# wk3-practice.net
KiCad netlist of a schematic drawn in EAGLE
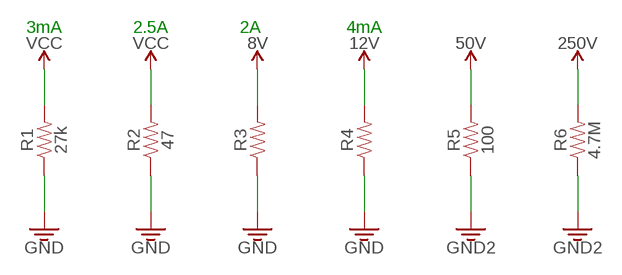
[diagram p0: schematic, sheet 1]

(export (version "E")
  (design (tool "Eeschema 10.0.6"))
  (components
    (comp (ref "R1")
      (value "27k")
      (footprint "eagle-import:AXIAL-0.3")
      (libsource (lib "eagle-import") (part "RESISTORAXIAL-0.3"))
    )
    (comp (ref "R2")
      (value "47")
      (footprint "eagle-import:AXIAL-0.3")
      (libsource (lib "eagle-import") (part "RESISTORAXIAL-0.3"))
    )
    (comp (ref "R3")
      (value "RESISTORAXIAL-0.3")
      (footprint "eagle-import:AXIAL-0.3")
      (libsource (lib "eagle-import") (part "RESISTORAXIAL-0.3"))
    )
    (comp (ref "R4")
      (value "RESISTORAXIAL-0.3")
      (footprint "eagle-import:AXIAL-0.3")
      (libsource (lib "eagle-import") (part "RESISTORAXIAL-0.3"))
    )
    (comp (ref "R5")
      (value "100")
      (footprint "eagle-import:AXIAL-0.3")
      (libsource (lib "eagle-import") (part "RESISTORAXIAL-0.3"))
    )
    (comp (ref "R6")
      (value "4.7M")
      (footprint "eagle-import:AXIAL-0.3")
      (libsource (lib "eagle-import") (part "RESISTORAXIAL-0.3"))
    )
  )
  (nets
    (net (code "1") (name "12V") (class "Default")
      (node (ref "R1") (pin "P$2") (pinfunction "2_P$2") (pintype "passive"))
      (node (ref "R2") (pin "P$2") (pinfunction "2_P$2") (pintype "passive"))
      (node (ref "R3") (pin "P$2") (pinfunction "2_P$2") (pintype "passive"))
      (node (ref "R4") (pin "P$2") (pinfunction "2_P$2") (pintype "passive"))
      (node (ref "R5") (pin "P$2") (pinfunction "2_P$2") (pintype "passive"))
      (node (ref "R6") (pin "P$2") (pinfunction "2_P$2") (pintype "passive"))
    )
    (net (code "2") (name "GND") (class "Default")
      (node (ref "R1") (pin "P$1") (pinfunction "1_P$1") (pintype "passive"))
      (node (ref "R2") (pin "P$1") (pinfunction "1_P$1") (pintype "passive"))
      (node (ref "R3") (pin "P$1") (pinfunction "1_P$1") (pintype "passive"))
      (node (ref "R4") (pin "P$1") (pinfunction "1_P$1") (pintype "passive"))
      (node (ref "R5") (pin "P$1") (pinfunction "1_P$1") (pintype "passive"))
      (node (ref "R6") (pin "P$1") (pinfunction "1_P$1") (pintype "passive"))
    )
  )
)
